# LaserDriver.net
KiCad netlist of a schematic drawn in EAGLE
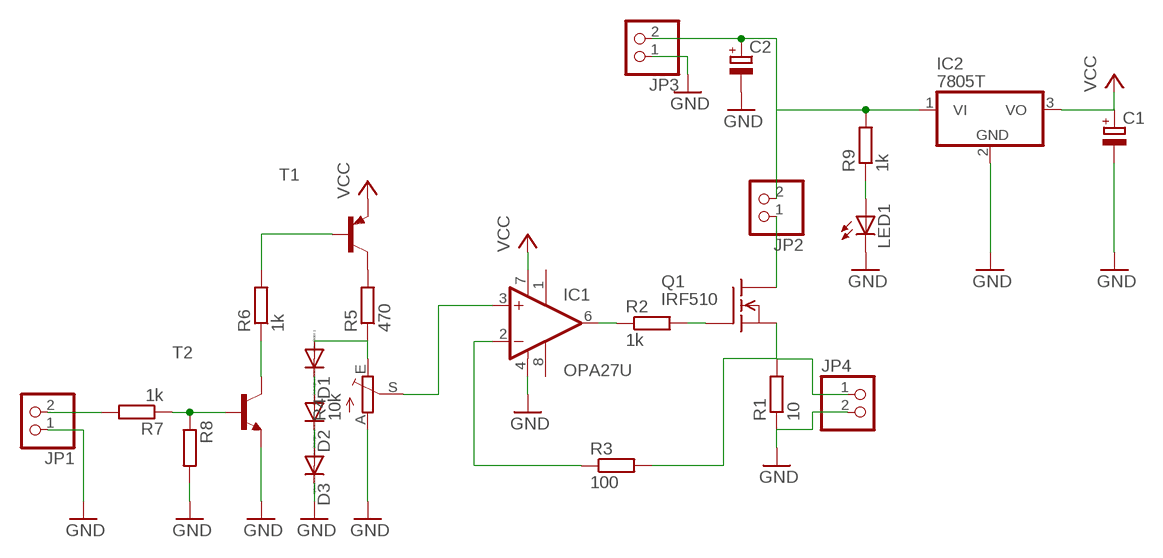
[diagram p0: schematic, sheet 1]

(export (version "E")
  (design (tool "Eeschema 10.0.6"))
  (components
    (comp (ref "C1")
      (value "CPOL-EUE5-10.5")
      (footprint "eagle-import:E5-10,5")
      (libsource (lib "eagle-import") (part "CPOL-EUE5-10.5"))
    )
    (comp (ref "C2")
      (value "CPOL-EUE5-10.5")
      (footprint "eagle-import:E5-10,5")
      (libsource (lib "eagle-import") (part "CPOL-EUE5-10.5"))
    )
    (comp (ref "D1")
      (value "DIODE-DO214AA")
      (footprint "eagle-import:DO214AA")
      (libsource (lib "eagle-import") (part "DIODE-DO214AA"))
    )
    (comp (ref "D2")
      (value "DIODE-DO214AA")
      (footprint "eagle-import:DO214AA")
      (libsource (lib "eagle-import") (part "DIODE-DO214AA"))
    )
    (comp (ref "D3")
      (value "DIODE-DO214AA")
      (footprint "eagle-import:DO214AA")
      (libsource (lib "eagle-import") (part "DIODE-DO214AA"))
    )
    (comp (ref "IC1")
      (value "OPA27U")
      (footprint "eagle-import:SO08")
      (libsource (lib "eagle-import") (part "OPA?U27"))
    )
    (comp (ref "IC2")
      (value "7805T")
      (footprint "eagle-import:TO220H")
      (libsource (lib "eagle-import") (part "78T05"))
    )
    (comp (ref "JP1")
      (value "PINHD-1X2")
      (footprint "eagle-import:1X02")
      (libsource (lib "eagle-import") (part "PINHD-1X2"))
    )
    (comp (ref "JP2")
      (value "PINHD-1X2")
      (footprint "eagle-import:1X02")
      (libsource (lib "eagle-import") (part "PINHD-1X2"))
    )
    (comp (ref "JP3")
      (value "PINHD-1X2")
      (footprint "eagle-import:1X02")
      (libsource (lib "eagle-import") (part "PINHD-1X2"))
    )
    (comp (ref "JP4")
      (value "PINHD-1X2")
      (footprint "eagle-import:1X02")
      (libsource (lib "eagle-import") (part "PINHD-1X2"))
    )
    (comp (ref "LED1")
      (value "LEDCHIP-LED0805")
      (footprint "eagle-import:CHIP-LED0805")
      (libsource (lib "eagle-import") (part "LEDCHIP-LED0805"))
    )
    (comp (ref "Q1")
      (value "IRF510")
      (footprint "eagle-import:TO220")
      (libsource (lib "eagle-import") (part "IRF510"))
    )
    (comp (ref "R1")
      (value "10")
      (footprint "eagle-import:0207_10")
      (libsource (lib "eagle-import") (part "R-EU_0207/10"))
    )
    (comp (ref "R2")
      (value "1k")
      (footprint "eagle-import:R1206")
      (libsource (lib "eagle-import") (part "R-EU_R1206"))
    )
    (comp (ref "R3")
      (value "100")
      (footprint "eagle-import:R1206")
      (libsource (lib "eagle-import") (part "R-EU_R1206"))
    )
    (comp (ref "R4")
      (value "10k")
      (footprint "eagle-import:SP19L")
      (libsource (lib "eagle-import") (part "TRIM_EU-B90P"))
    )
    (comp (ref "R5")
      (value "470")
      (footprint "eagle-import:R1206")
      (libsource (lib "eagle-import") (part "R-EU_R1206"))
    )
    (comp (ref "R6")
      (value "1k")
      (footprint "eagle-import:R1206")
      (libsource (lib "eagle-import") (part "R-EU_R1206"))
    )
    (comp (ref "R7")
      (value "1k")
      (footprint "eagle-import:R1206")
      (libsource (lib "eagle-import") (part "R-EU_R1206"))
    )
    (comp (ref "R8")
      (value "R-EU_R1206")
      (footprint "eagle-import:R1206")
      (libsource (lib "eagle-import") (part "R-EU_R1206"))
    )
    (comp (ref "R9")
      (value "1k")
      (footprint "eagle-import:R1206")
      (libsource (lib "eagle-import") (part "R-EU_R1206"))
    )
    (comp (ref "T1")
      (value "MMBT3906LT1-PNP-SOT23-BEC")
      (footprint "eagle-import:SOT23-BEC")
      (libsource (lib "eagle-import") (part "-PNP-SOT23-BECMMBT3906LT1"))
    )
    (comp (ref "T2")
      (value "BC817-16-NPN-SOT23-BEC")
      (footprint "eagle-import:SOT23-BEC")
      (libsource (lib "eagle-import") (part "-NPN-SOT23-BECBC817-16"))
    )
  )
  (nets
    (net (code "1") (name "GND") (class "Default")
      (node (ref "C1") (pin "-") (pinfunction "-_-") (pintype "passive"))
      (node (ref "C2") (pin "-") (pinfunction "-_-") (pintype "passive"))
      (node (ref "D3") (pin "C") (pinfunction "C_C") (pintype "passive"))
      (node (ref "IC1") (pin "4") (pinfunction "V-_4") (pintype "power_in"))
      (node (ref "IC2") (pin "2") (pinfunction "GND_2") (pintype "passive"))
      (node (ref "JP1") (pin "1") (pinfunction "1_1") (pintype "passive"))
      (node (ref "JP3") (pin "1") (pinfunction "1_1") (pintype "passive"))
      (node (ref "JP4") (pin "2") (pinfunction "2_2") (pintype "passive"))
      (node (ref "LED1") (pin "C") (pinfunction "C_C") (pintype "passive"))
      (node (ref "R1") (pin "1") (pinfunction "1_1") (pintype "passive"))
      (node (ref "R4") (pin "A") (pinfunction "A_A") (pintype "passive"))
      (node (ref "R8") (pin "2") (pinfunction "2_2") (pintype "passive"))
      (node (ref "T2") (pin "E") (pinfunction "E_E") (pintype "passive"))
    )
    (net (code "2") (name "Net-(D1-PadA)") (class "Default")
      (node (ref "D1") (pin "A") (pinfunction "A_A") (pintype "passive"))
      (node (ref "R4") (pin "E") (pinfunction "E_E") (pintype "passive"))
      (node (ref "R5") (pin "1") (pinfunction "1_1") (pintype "passive"))
    )
    (net (code "3") (name "Net-(D1-PadC)") (class "Default")
      (node (ref "D1") (pin "C") (pinfunction "C_C") (pintype "passive"))
      (node (ref "D2") (pin "A") (pinfunction "A_A") (pintype "passive"))
    )
    (net (code "4") (name "Net-(D2-PadC)") (class "Default")
      (node (ref "D2") (pin "C") (pinfunction "C_C") (pintype "passive"))
      (node (ref "D3") (pin "A") (pinfunction "A_A") (pintype "passive"))
    )
    (net (code "5") (name "Net-(IC1-+IN)") (class "Default")
      (node (ref "IC1") (pin "3") (pinfunction "+IN_3") (pintype "input"))
      (node (ref "R4") (pin "S") (pinfunction "S_S") (pintype "passive"))
    )
    (net (code "6") (name "Net-(IC1--IN)") (class "Default")
      (node (ref "IC1") (pin "2") (pinfunction "-IN_2") (pintype "input"))
      (node (ref "R3") (pin "1") (pinfunction "1_1") (pintype "passive"))
    )
    (net (code "7") (name "Net-(IC1-OUT)") (class "Default")
      (node (ref "IC1") (pin "6") (pinfunction "OUT_6") (pintype "output"))
      (node (ref "R2") (pin "1") (pinfunction "1_1") (pintype "passive"))
    )
    (net (code "8") (name "Net-(IC2-VI)") (class "Default")
      (node (ref "C2") (pin "+") (pinfunction "+_+") (pintype "passive"))
      (node (ref "IC2") (pin "1") (pinfunction "VI_1") (pintype "input"))
      (node (ref "JP2") (pin "2") (pinfunction "2_2") (pintype "passive"))
      (node (ref "JP3") (pin "2") (pinfunction "2_2") (pintype "passive"))
      (node (ref "R9") (pin "2") (pinfunction "2_2") (pintype "passive"))
    )
    (net (code "9") (name "Net-(JP1-Pad2)") (class "Default")
      (node (ref "JP1") (pin "2") (pinfunction "2_2") (pintype "passive"))
      (node (ref "R7") (pin "2") (pinfunction "2_2") (pintype "passive"))
    )
    (net (code "10") (name "Net-(LED1-PadA)") (class "Default")
      (node (ref "LED1") (pin "A") (pinfunction "A_A") (pintype "passive"))
      (node (ref "R9") (pin "1") (pinfunction "1_1") (pintype "passive"))
    )
    (net (code "11") (name "Net-(Q1-D)") (class "Default")
      (node (ref "JP2") (pin "1") (pinfunction "1_1") (pintype "passive"))
      (node (ref "Q1") (pin "2") (pinfunction "D_2") (pintype "passive"))
    )
    (net (code "12") (name "Net-(Q1-G)") (class "Default")
      (node (ref "Q1") (pin "1") (pinfunction "G_1") (pintype "passive"))
      (node (ref "R2") (pin "2") (pinfunction "2_2") (pintype "passive"))
    )
    (net (code "13") (name "Net-(Q1-S)") (class "Default")
      (node (ref "JP4") (pin "1") (pinfunction "1_1") (pintype "passive"))
      (node (ref "Q1") (pin "3") (pinfunction "S_3") (pintype "passive"))
      (node (ref "R1") (pin "2") (pinfunction "2_2") (pintype "passive"))
      (node (ref "R3") (pin "2") (pinfunction "2_2") (pintype "passive"))
    )
    (net (code "14") (name "Net-(R5-Pad2)") (class "Default")
      (node (ref "R5") (pin "2") (pinfunction "2_2") (pintype "passive"))
      (node (ref "T1") (pin "C") (pinfunction "C_C") (pintype "passive"))
    )
    (net (code "15") (name "Net-(R6-Pad1)") (class "Default")
      (node (ref "R6") (pin "1") (pinfunction "1_1") (pintype "passive"))
      (node (ref "T2") (pin "C") (pinfunction "C_C") (pintype "passive"))
    )
    (net (code "16") (name "Net-(R6-Pad2)") (class "Default")
      (node (ref "R6") (pin "2") (pinfunction "2_2") (pintype "passive"))
      (node (ref "T1") (pin "B") (pinfunction "B_B") (pintype "passive"))
    )
    (net (code "17") (name "Net-(R7-Pad1)") (class "Default")
      (node (ref "R7") (pin "1") (pinfunction "1_1") (pintype "passive"))
      (node (ref "R8") (pin "1") (pinfunction "1_1") (pintype "passive"))
      (node (ref "T2") (pin "B") (pinfunction "B_B") (pintype "passive"))
    )
    (net (code "18") (name "VCC") (class "Default")
      (node (ref "C1") (pin "+") (pinfunction "+_+") (pintype "passive"))
      (node (ref "IC1") (pin "7") (pinfunction "V+_7") (pintype "power_in"))
      (node (ref "IC2") (pin "3") (pinfunction "VO_3") (pintype "passive"))
      (node (ref "T1") (pin "E") (pinfunction "E_E") (pintype "passive"))
    )
    (net (code "19") (name "unconnected-(IC1-OFF1-Pad1)") (class "Default")
      (node (ref "IC1") (pin "1") (pinfunction "OFF1_1") (pintype "passive"))
    )
    (net (code "20") (name "unconnected-(IC1-OFF2-Pad8)") (class "Default")
      (node (ref "IC1") (pin "8") (pinfunction "OFF2_8") (pintype "passive"))
    )
  )
)
